# main.net
KiCad netlist of a schematic drawn in EAGLE
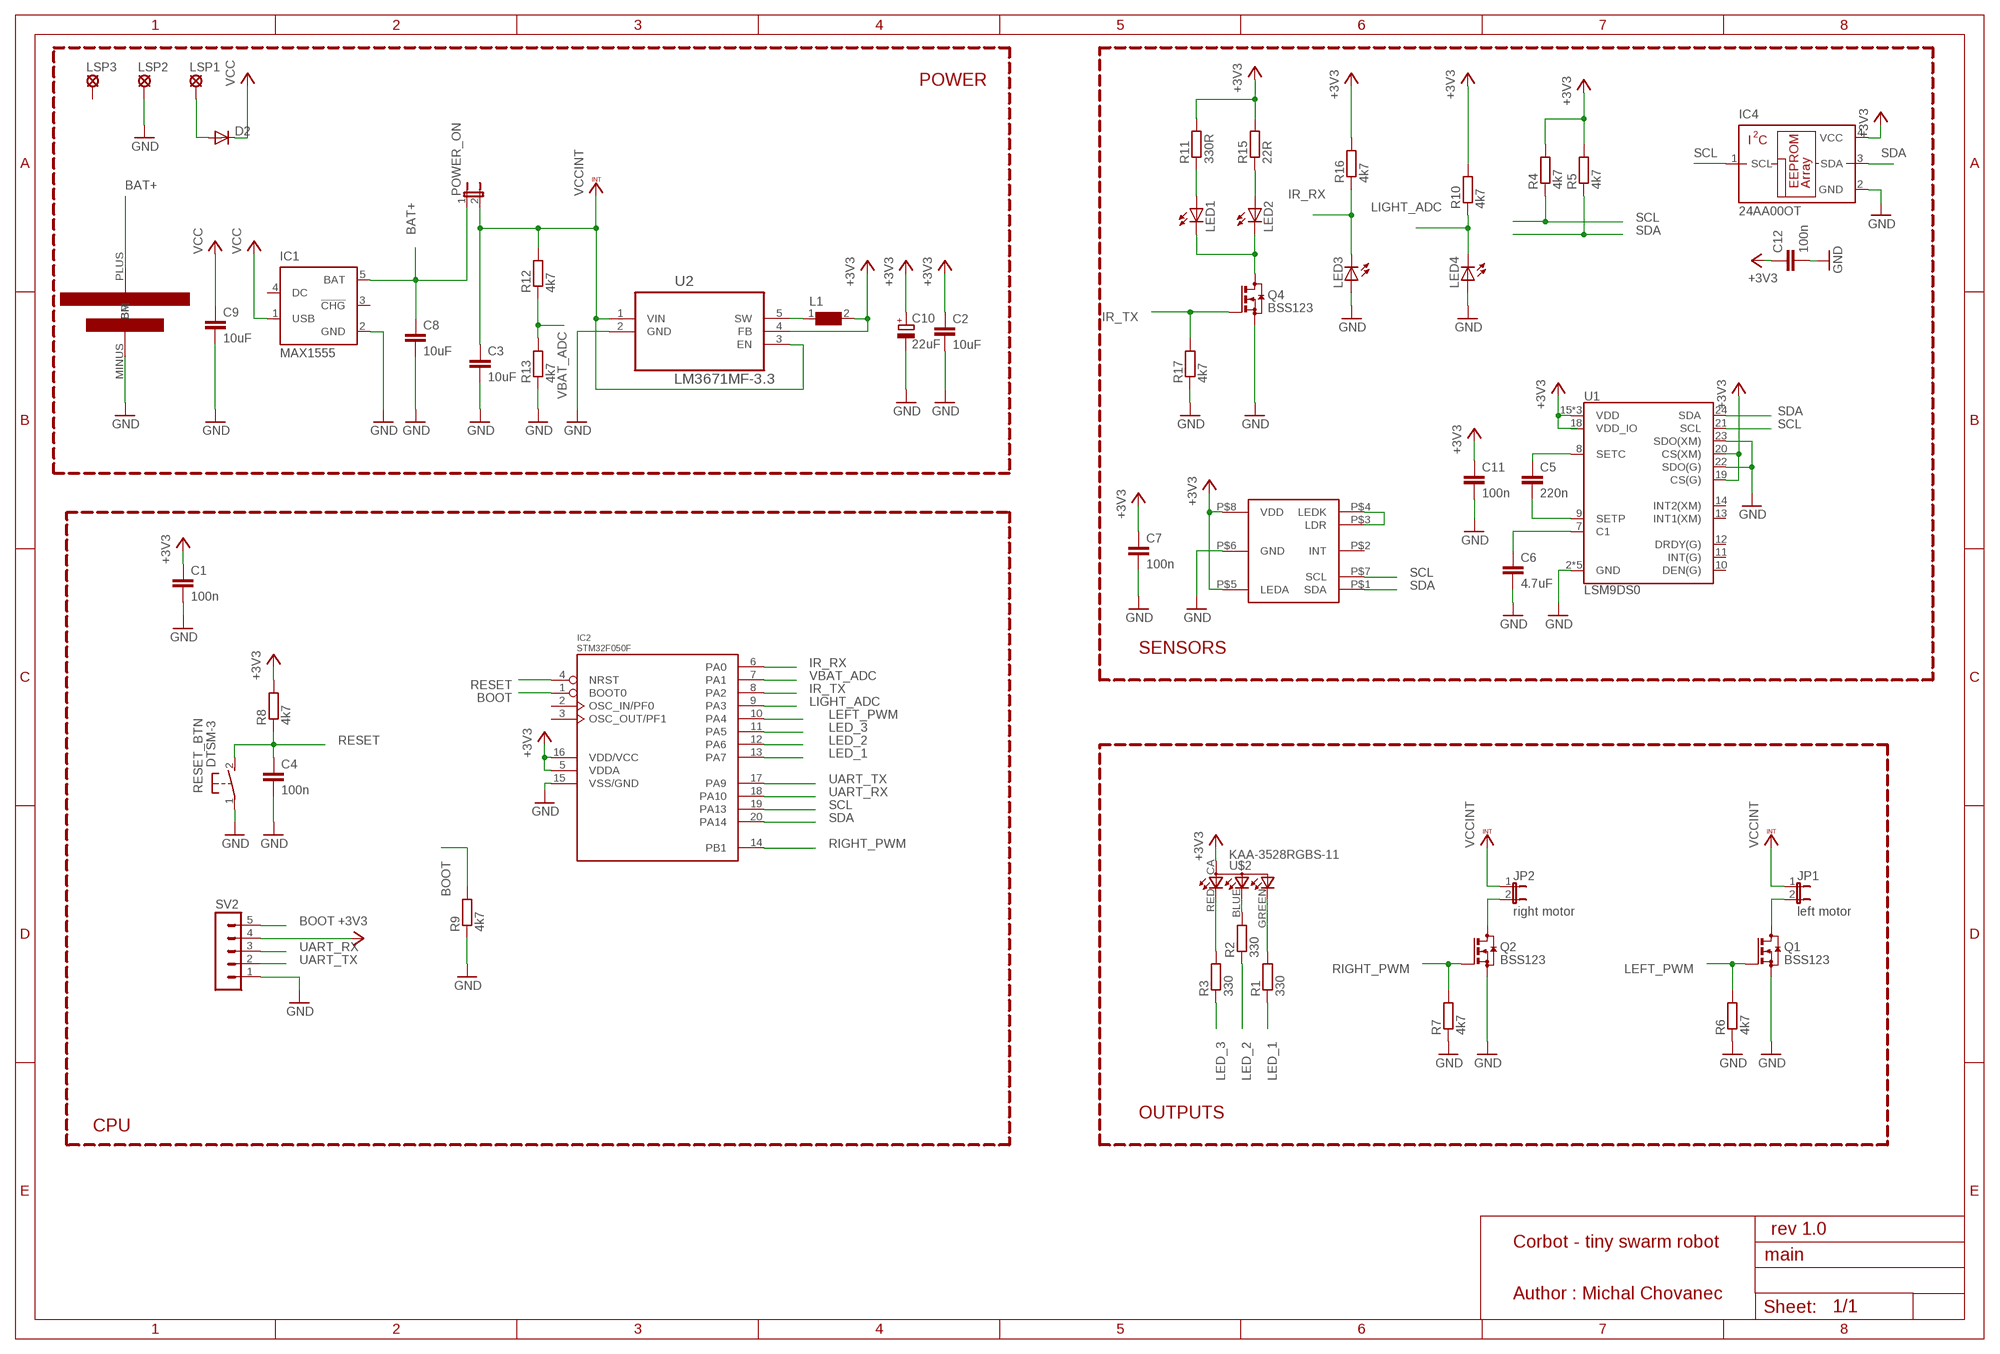
[diagram p0: schematic, sheet 1]

(export (version "E")
  (design (tool "Eeschema 10.0.6"))
  (components
    (comp (ref "C1")
      (value "100n")
      (footprint "eagle-import:C0805")
      (libsource (lib "eagle-import") (part "C-EUC0805"))
    )
    (comp (ref "C2")
      (value "10uF")
      (footprint "eagle-import:C0805")
      (libsource (lib "eagle-import") (part "C-EUC0805"))
    )
    (comp (ref "C3")
      (value "10uF")
      (footprint "eagle-import:C0805")
      (libsource (lib "eagle-import") (part "C-EUC0805"))
    )
    (comp (ref "C4")
      (value "100n")
      (footprint "eagle-import:C0805")
      (libsource (lib "eagle-import") (part "C-EUC0805"))
    )
    (comp (ref "C5")
      (value "220n")
      (footprint "eagle-import:C0805")
      (libsource (lib "eagle-import") (part "C-EUC0805"))
    )
    (comp (ref "C6")
      (value "4.7uF")
      (footprint "eagle-import:C0805")
      (libsource (lib "eagle-import") (part "C-EUC0805"))
    )
    (comp (ref "C7")
      (value "100n")
      (footprint "eagle-import:C0805")
      (libsource (lib "eagle-import") (part "C-EUC0805"))
    )
    (comp (ref "C8")
      (value "10uF")
      (footprint "eagle-import:C0805")
      (libsource (lib "eagle-import") (part "C-EUC0805"))
    )
    (comp (ref "C9")
      (value "10uF")
      (footprint "eagle-import:C0805")
      (libsource (lib "eagle-import") (part "C-EUC0805"))
    )
    (comp (ref "C10")
      (value "22uF")
      (footprint "eagle-import:153CLV-0505")
      (libsource (lib "eagle-import") (part "CPOL-EU153CLV-0505"))
    )
    (comp (ref "C11")
      (value "100n")
      (footprint "eagle-import:C0805")
      (libsource (lib "eagle-import") (part "C-EUC0805"))
    )
    (comp (ref "C12")
      (value "100n")
      (footprint "eagle-import:C0805")
      (libsource (lib "eagle-import") (part "C-EUC0805"))
    )
    (comp (ref "D2")
      (value "DIODE-DO-214AC")
      (footprint "eagle-import:DO-214AC")
      (libsource (lib "eagle-import") (part "DIODE-DO-214AC"))
    )
    (comp (ref "IC1")
      (value "MAX1555")
      (footprint "eagle-import:SOT23-5L")
      (fields (field (name "MF") "MAXIM") (field (name "MPN") "MAX1555EZK+T"))
      (libsource (lib "eagle-import") (part "MAX1555"))
    )
    (comp (ref "IC2")
      (value "STM32F050F")
      (footprint "eagle-import:TSSOP20")
      (libsource (lib "eagle-import") (part "STM32F050F"))
    )
    (comp (ref "IC4")
      (value "24AA00OT")
      (footprint "eagle-import:SOT23-5L")
      (fields (field (name "MF") "MICROCHIP") (field (name "MPN") "24AA00T-I/OTG"))
      (libsource (lib "eagle-import") (part "2400OTAA"))
    )
    (comp (ref "JP1")
      (value "left motor")
      (footprint "eagle-import:JP1")
      (libsource (lib "eagle-import") (part "JP1E"))
    )
    (comp (ref "JP2")
      (value "right motor")
      (footprint "eagle-import:JP1")
      (libsource (lib "eagle-import") (part "JP1E"))
    )
    (comp (ref "L1")
      (value "WE-LQ-744032002_M")
      (footprint "eagle-import:WE-LQ_M")
      (fields (field (name "MPN") "744032002 "))
      (libsource (lib "eagle-import") (part "WE-LQ_M-744032002"))
    )
    (comp (ref "LED1")
      (value "LEDCHIPLED_1206")
      (footprint "eagle-import:CHIPLED_1206")
      (libsource (lib "eagle-import") (part "LEDCHIPLED_1206"))
    )
    (comp (ref "LED2")
      (value "LEDCHIPLED_1206")
      (footprint "eagle-import:CHIPLED_1206")
      (libsource (lib "eagle-import") (part "LEDCHIPLED_1206"))
    )
    (comp (ref "LED3")
      (value "LEDCHIPLED_1206")
      (footprint "eagle-import:CHIPLED_1206")
      (libsource (lib "eagle-import") (part "LEDCHIPLED_1206"))
    )
    (comp (ref "LED4")
      (value "LEDCHIPLED_1206")
      (footprint "eagle-import:CHIPLED_1206")
      (libsource (lib "eagle-import") (part "LEDCHIPLED_1206"))
    )
    (comp (ref "LSP1")
      (value "LSP13")
      (footprint "eagle-import:LSP13")
      (libsource (lib "eagle-import") (part "LSP13"))
    )
    (comp (ref "LSP2")
      (value "LSP13")
      (footprint "eagle-import:LSP13")
      (libsource (lib "eagle-import") (part "LSP13"))
    )
    (comp (ref "LSP3")
      (value "LSP13")
      (footprint "eagle-import:LSP13")
      (libsource (lib "eagle-import") (part "LSP13"))
    )
    (comp (ref "POWER_ON")
      (value "JP1E")
      (footprint "eagle-import:JP1")
      (libsource (lib "eagle-import") (part "JP1E"))
    )
    (comp (ref "Q1")
      (value "BSS123")
      (footprint "eagle-import:SOT23")
      (libsource (lib "eagle-import") (part "BSS123"))
    )
    (comp (ref "Q2")
      (value "BSS123")
      (footprint "eagle-import:SOT23")
      (libsource (lib "eagle-import") (part "BSS123"))
    )
    (comp (ref "Q4")
      (value "BSS123")
      (footprint "eagle-import:SOT23")
      (libsource (lib "eagle-import") (part "BSS123"))
    )
    (comp (ref "R1")
      (value "330")
      (footprint "eagle-import:M0805")
      (libsource (lib "eagle-import") (part "R-EU_M0805"))
    )
    (comp (ref "R2")
      (value "330")
      (footprint "eagle-import:M0805")
      (libsource (lib "eagle-import") (part "R-EU_M0805"))
    )
    (comp (ref "R3")
      (value "330")
      (footprint "eagle-import:M0805")
      (libsource (lib "eagle-import") (part "R-EU_M0805"))
    )
    (comp (ref "R4")
      (value "4k7")
      (footprint "eagle-import:M0805")
      (libsource (lib "eagle-import") (part "R-EU_M0805"))
    )
    (comp (ref "R5")
      (value "4k7")
      (footprint "eagle-import:M0805")
      (libsource (lib "eagle-import") (part "R-EU_M0805"))
    )
    (comp (ref "R6")
      (value "4k7")
      (footprint "eagle-import:M0805")
      (libsource (lib "eagle-import") (part "R-EU_M0805"))
    )
    (comp (ref "R7")
      (value "4k7")
      (footprint "eagle-import:M0805")
      (libsource (lib "eagle-import") (part "R-EU_M0805"))
    )
    (comp (ref "R8")
      (value "4k7")
      (footprint "eagle-import:M0805")
      (libsource (lib "eagle-import") (part "R-EU_M0805"))
    )
    (comp (ref "R9")
      (value "4k7")
      (footprint "eagle-import:M0805")
      (libsource (lib "eagle-import") (part "R-EU_M0805"))
    )
    (comp (ref "R10")
      (value "4k7")
      (footprint "eagle-import:M0805")
      (libsource (lib "eagle-import") (part "R-EU_M0805"))
    )
    (comp (ref "R11")
      (value "330R")
      (footprint "eagle-import:M0805")
      (libsource (lib "eagle-import") (part "R-EU_M0805"))
    )
    (comp (ref "R12")
      (value "4k7")
      (footprint "eagle-import:M0805")
      (libsource (lib "eagle-import") (part "R-EU_M0805"))
    )
    (comp (ref "R13")
      (value "4k7")
      (footprint "eagle-import:M0805")
      (libsource (lib "eagle-import") (part "R-EU_M0805"))
    )
    (comp (ref "R15")
      (value "22R")
      (footprint "eagle-import:M0805")
      (libsource (lib "eagle-import") (part "R-EU_M0805"))
    )
    (comp (ref "R16")
      (value "4k7")
      (footprint "eagle-import:M0805")
      (libsource (lib "eagle-import") (part "R-EU_M0805"))
    )
    (comp (ref "R17")
      (value "4k7")
      (footprint "eagle-import:M0805")
      (libsource (lib "eagle-import") (part "R-EU_M0805"))
    )
    (comp (ref "RESET_BTN")
      (value "DTSM-3")
      (footprint "eagle-import:DTSM-3")
      (libsource (lib "eagle-import") (part "DTSM-3"))
    )
    (comp (ref "SV2")
      (value "MA05-1")
      (footprint "eagle-import:MA05-1")
      (libsource (lib "eagle-import") (part "MA05-1"))
    )
    (comp (ref "U$1")
      (value "SMTU_2450N")
      (footprint "eagle-import:SMTU_2450N")
      (libsource (lib "eagle-import") (part "SMTU_2450N"))
    )
    (comp (ref "U$2")
      (value "KAA-3528RGBS-11")
      (footprint "eagle-import:LED-RGB")
      (libsource (lib "eagle-import") (part "KAA-3528RGBS-11"))
    )
    (comp (ref "U$3")
      (value "APDS9950")
      (footprint "eagle-import:APDS9950")
      (libsource (lib "eagle-import") (part "APDS9950"))
    )
    (comp (ref "U1")
      (value "LSM9DS0")
      (footprint "eagle-import:LGA-24")
      (libsource (lib "eagle-import") (part "LSM9DS0"))
    )
    (comp (ref "U2")
      (value "LM3671MF-3.3")
      (footprint "eagle-import:SOT95P284X122-5N")
      (libsource (lib "eagle-import") (part "LM3671MF-3.3"))
    )
  )
  (nets
    (net (code "1") (name "+3V3") (class "Default")
      (node (ref "C1") (pin "1") (pinfunction "1_1") (pintype "passive"))
      (node (ref "C10") (pin "+") (pinfunction "+_+") (pintype "passive"))
      (node (ref "C11") (pin "1") (pinfunction "1_1") (pintype "passive"))
      (node (ref "C12") (pin "1") (pinfunction "1_1") (pintype "passive"))
      (node (ref "C2") (pin "1") (pinfunction "1_1") (pintype "passive"))
      (node (ref "C7") (pin "1") (pinfunction "1_1") (pintype "passive"))
      (node (ref "IC2") (pin "16") (pinfunction "VDD/VCC_16") (pintype "power_in"))
      (node (ref "IC2") (pin "5") (pinfunction "VDDA_5") (pintype "power_in"))
      (node (ref "IC4") (pin "4") (pinfunction "VCC_4") (pintype "power_in"))
      (node (ref "L1") (pin "2") (pinfunction "2_2") (pintype "passive"))
      (node (ref "R10") (pin "2") (pinfunction "2_2") (pintype "passive"))
      (node (ref "R11") (pin "2") (pinfunction "2_2") (pintype "passive"))
      (node (ref "R15") (pin "2") (pinfunction "2_2") (pintype "passive"))
      (node (ref "R16") (pin "2") (pinfunction "2_2") (pintype "passive"))
      (node (ref "R4") (pin "2") (pinfunction "2_2") (pintype "passive"))
      (node (ref "R5") (pin "2") (pinfunction "2_2") (pintype "passive"))
      (node (ref "R8") (pin "2") (pinfunction "2_2") (pintype "passive"))
      (node (ref "SV2") (pin "4") (pinfunction "4_4") (pintype "passive"))
      (node (ref "U$2") (pin "CA") (pinfunction "A_CA") (pintype "passive"))
      (node (ref "U$3") (pin "P$5") (pinfunction "LEDA_P$5") (pintype "bidirectional"))
      (node (ref "U$3") (pin "P$8") (pinfunction "VDD_P$8") (pintype "bidirectional"))
      (node (ref "U1") (pin "15") (pinfunction "VDD_15") (pintype "bidirectional"))
      (node (ref "U1") (pin "16") (pinfunction "VDD_16") (pintype "bidirectional"))
      (node (ref "U1") (pin "17") (pinfunction "VDD_17") (pintype "bidirectional"))
      (node (ref "U1") (pin "19") (pinfunction "CS(G)_19") (pintype "bidirectional"))
      (node (ref "U1") (pin "20") (pinfunction "CS(XM)_20") (pintype "bidirectional"))
      (node (ref "U2") (pin "4") (pinfunction "FB_4") (pintype "passive"))
    )
    (net (code "2") (name "/BAT+") (class "Default")
      (node (ref "C8") (pin "1") (pinfunction "1_1") (pintype "passive"))
      (node (ref "IC1") (pin "5") (pinfunction "BAT_5") (pintype "passive"))
      (node (ref "POWER_ON") (pin "1") (pinfunction "1_1") (pintype "passive"))
      (node (ref "U$1") (pin "PLUS") (pinfunction "BP_PLUS") (pintype "bidirectional"))
    )
    (net (code "3") (name "/BOOT") (class "Default")
      (node (ref "IC2") (pin "1") (pinfunction "BOOT0_1") (pintype "bidirectional"))
      (node (ref "R9") (pin "2") (pinfunction "2_2") (pintype "passive"))
      (node (ref "SV2") (pin "5") (pinfunction "5_5") (pintype "passive"))
    )
    (net (code "4") (name "/IR_RX") (class "Default")
      (node (ref "IC2") (pin "6") (pinfunction "PA0_6") (pintype "bidirectional"))
      (node (ref "LED3") (pin "C") (pinfunction "C_C") (pintype "passive"))
      (node (ref "R16") (pin "1") (pinfunction "1_1") (pintype "passive"))
    )
    (net (code "5") (name "/IR_TX") (class "Default")
      (node (ref "IC2") (pin "8") (pinfunction "PA2_8") (pintype "bidirectional"))
      (node (ref "Q4") (pin "1") (pinfunction "G_1") (pintype "passive"))
      (node (ref "R17") (pin "2") (pinfunction "2_2") (pintype "passive"))
    )
    (net (code "6") (name "/LED_1") (class "Default")
      (node (ref "IC2") (pin "13") (pinfunction "PA7_13") (pintype "bidirectional"))
      (node (ref "R1") (pin "1") (pinfunction "1_1") (pintype "passive"))
    )
    (net (code "7") (name "/LED_2") (class "Default")
      (node (ref "IC2") (pin "12") (pinfunction "PA6_12") (pintype "bidirectional"))
      (node (ref "R2") (pin "1") (pinfunction "1_1") (pintype "passive"))
    )
    (net (code "8") (name "/LED_3") (class "Default")
      (node (ref "IC2") (pin "11") (pinfunction "PA5_11") (pintype "bidirectional"))
      (node (ref "R3") (pin "1") (pinfunction "1_1") (pintype "passive"))
    )
    (net (code "9") (name "/LEFT_PWM") (class "Default")
      (node (ref "IC2") (pin "10") (pinfunction "PA4_10") (pintype "bidirectional"))
      (node (ref "Q1") (pin "1") (pinfunction "G_1") (pintype "passive"))
      (node (ref "R6") (pin "2") (pinfunction "2_2") (pintype "passive"))
    )
    (net (code "10") (name "/LIGHT_ADC") (class "Default")
      (node (ref "IC2") (pin "9") (pinfunction "PA3_9") (pintype "bidirectional"))
      (node (ref "LED4") (pin "C") (pinfunction "C_C") (pintype "passive"))
      (node (ref "R10") (pin "1") (pinfunction "1_1") (pintype "passive"))
    )
    (net (code "11") (name "/RESET") (class "Default")
      (node (ref "C4") (pin "1") (pinfunction "1_1") (pintype "passive"))
      (node (ref "IC2") (pin "4") (pinfunction "NRST_4") (pintype "bidirectional"))
      (node (ref "R8") (pin "1") (pinfunction "1_1") (pintype "passive"))
      (node (ref "RESET_BTN") (pin "2") (pinfunction "2_2") (pintype "passive"))
    )
    (net (code "12") (name "/RIGHT_PWM") (class "Default")
      (node (ref "IC2") (pin "14") (pinfunction "PB1_14") (pintype "bidirectional"))
      (node (ref "Q2") (pin "1") (pinfunction "G_1") (pintype "passive"))
      (node (ref "R7") (pin "2") (pinfunction "2_2") (pintype "passive"))
    )
    (net (code "13") (name "/SCL") (class "Default")
      (node (ref "IC2") (pin "19") (pinfunction "PA13_19") (pintype "bidirectional"))
      (node (ref "IC4") (pin "1") (pinfunction "SCL_1") (pintype "input"))
      (node (ref "R4") (pin "1") (pinfunction "1_1") (pintype "passive"))
      (node (ref "U$3") (pin "P$7") (pinfunction "SCL_P$7") (pintype "bidirectional"))
      (node (ref "U1") (pin "21") (pinfunction "SCL_21") (pintype "bidirectional"))
    )
    (net (code "14") (name "/SDA") (class "Default")
      (node (ref "IC2") (pin "20") (pinfunction "PA14_20") (pintype "bidirectional"))
      (node (ref "IC4") (pin "3") (pinfunction "SDA_3") (pintype "bidirectional"))
      (node (ref "R5") (pin "1") (pinfunction "1_1") (pintype "passive"))
      (node (ref "U$3") (pin "P$1") (pinfunction "SDA_P$1") (pintype "bidirectional"))
      (node (ref "U1") (pin "24") (pinfunction "SDA_24") (pintype "bidirectional"))
    )
    (net (code "15") (name "/UART_RX") (class "Default")
      (node (ref "IC2") (pin "18") (pinfunction "PA10_18") (pintype "bidirectional"))
      (node (ref "SV2") (pin "3") (pinfunction "3_3") (pintype "passive"))
    )
    (net (code "16") (name "/UART_TX") (class "Default")
      (node (ref "IC2") (pin "17") (pinfunction "PA9_17") (pintype "bidirectional"))
      (node (ref "SV2") (pin "2") (pinfunction "2_2") (pintype "passive"))
    )
    (net (code "17") (name "/VBAT_ADC") (class "Default")
      (node (ref "IC2") (pin "7") (pinfunction "PA1_7") (pintype "bidirectional"))
      (node (ref "R12") (pin "1") (pinfunction "1_1") (pintype "passive"))
      (node (ref "R13") (pin "2") (pinfunction "2_2") (pintype "passive"))
    )
    (net (code "18") (name "GND") (class "Default")
      (node (ref "C1") (pin "2") (pinfunction "2_2") (pintype "passive"))
      (node (ref "C10") (pin "-") (pinfunction "-_-") (pintype "passive"))
      (node (ref "C11") (pin "2") (pinfunction "2_2") (pintype "passive"))
      (node (ref "C12") (pin "2") (pinfunction "2_2") (pintype "passive"))
      (node (ref "C2") (pin "2") (pinfunction "2_2") (pintype "passive"))
      (node (ref "C3") (pin "2") (pinfunction "2_2") (pintype "passive"))
      (node (ref "C4") (pin "2") (pinfunction "2_2") (pintype "passive"))
      (node (ref "C6") (pin "2") (pinfunction "2_2") (pintype "passive"))
      (node (ref "C7") (pin "2") (pinfunction "2_2") (pintype "passive"))
      (node (ref "C8") (pin "2") (pinfunction "2_2") (pintype "passive"))
      (node (ref "C9") (pin "2") (pinfunction "2_2") (pintype "passive"))
      (node (ref "IC1") (pin "2") (pinfunction "GND_2") (pintype "power_in"))
      (node (ref "IC2") (pin "15") (pinfunction "VSS/GND_15") (pintype "power_in"))
      (node (ref "IC4") (pin "2") (pinfunction "GND_2") (pintype "power_in"))
      (node (ref "LED3") (pin "A") (pinfunction "A_A") (pintype "passive"))
      (node (ref "LED4") (pin "A") (pinfunction "A_A") (pintype "passive"))
      (node (ref "LSP2") (pin "MP") (pinfunction "MP_MP") (pintype "passive"))
      (node (ref "Q1") (pin "2") (pinfunction "S_2") (pintype "passive"))
      (node (ref "Q2") (pin "2") (pinfunction "S_2") (pintype "passive"))
      (node (ref "Q4") (pin "2") (pinfunction "S_2") (pintype "passive"))
      (node (ref "R13") (pin "1") (pinfunction "1_1") (pintype "passive"))
      (node (ref "R17") (pin "1") (pinfunction "1_1") (pintype "passive"))
      (node (ref "R6") (pin "1") (pinfunction "1_1") (pintype "passive"))
      (node (ref "R7") (pin "1") (pinfunction "1_1") (pintype "passive"))
      (node (ref "R9") (pin "1") (pinfunction "1_1") (pintype "passive"))
      (node (ref "RESET_BTN") (pin "1") (pinfunction "1_1") (pintype "passive"))
      (node (ref "SV2") (pin "1") (pinfunction "1_1") (pintype "passive"))
      (node (ref "U$1") (pin "MINUS") (pinfunction "BM_MINUS") (pintype "bidirectional"))
      (node (ref "U$3") (pin "P$6") (pinfunction "GND_P$6") (pintype "bidirectional"))
      (node (ref "U1") (pin "2") (pinfunction "GND_2") (pintype "bidirectional"))
      (node (ref "U1") (pin "22") (pinfunction "SDO(G)_22") (pintype "bidirectional"))
      (node (ref "U1") (pin "23") (pinfunction "SDO(XM)_23") (pintype "bidirectional"))
      (node (ref "U1") (pin "3") (pinfunction "GND_3") (pintype "bidirectional"))
      (node (ref "U1") (pin "4") (pinfunction "GND_4") (pintype "bidirectional"))
      (node (ref "U1") (pin "5") (pinfunction "GND_5") (pintype "bidirectional"))
      (node (ref "U1") (pin "6") (pinfunction "GND_6") (pintype "bidirectional"))
      (node (ref "U2") (pin "2") (pinfunction "GND_2") (pintype "passive"))
    )
    (net (code "19") (name "Net-(D2-PadA)") (class "Default")
      (node (ref "D2") (pin "A") (pinfunction "A_A") (pintype "passive"))
      (node (ref "LSP1") (pin "MP") (pinfunction "MP_MP") (pintype "passive"))
    )
    (net (code "20") (name "Net-(LED1-PadA)") (class "Default")
      (node (ref "LED1") (pin "A") (pinfunction "A_A") (pintype "passive"))
      (node (ref "R11") (pin "1") (pinfunction "1_1") (pintype "passive"))
    )
    (net (code "21") (name "Net-(LED2-PadA)") (class "Default")
      (node (ref "LED2") (pin "A") (pinfunction "A_A") (pintype "passive"))
      (node (ref "R15") (pin "1") (pinfunction "1_1") (pintype "passive"))
    )
    (net (code "22") (name "Net-(Q1-D)") (class "Default")
      (node (ref "JP1") (pin "2") (pinfunction "2_2") (pintype "passive"))
      (node (ref "Q1") (pin "3") (pinfunction "D_3") (pintype "passive"))
    )
    (net (code "23") (name "Net-(Q2-D)") (class "Default")
      (node (ref "JP2") (pin "2") (pinfunction "2_2") (pintype "passive"))
      (node (ref "Q2") (pin "3") (pinfunction "D_3") (pintype "passive"))
    )
    (net (code "24") (name "Net-(Q4-D)") (class "Default")
      (node (ref "LED1") (pin "C") (pinfunction "C_C") (pintype "passive"))
      (node (ref "LED2") (pin "C") (pinfunction "C_C") (pintype "passive"))
      (node (ref "Q4") (pin "3") (pinfunction "D_3") (pintype "passive"))
    )
    (net (code "25") (name "Net-(U$2-CBLUE)") (class "Default")
      (node (ref "R2") (pin "2") (pinfunction "2_2") (pintype "passive"))
      (node (ref "U$2") (pin "BLUE") (pinfunction "CBLUE_BLUE") (pintype "passive"))
    )
    (net (code "26") (name "Net-(U$2-CGREEN)") (class "Default")
      (node (ref "R1") (pin "2") (pinfunction "2_2") (pintype "passive"))
      (node (ref "U$2") (pin "GREEN") (pinfunction "CGREEN_GREEN") (pintype "passive"))
    )
    (net (code "27") (name "Net-(U$2-CRED)") (class "Default")
      (node (ref "R3") (pin "2") (pinfunction "2_2") (pintype "passive"))
      (node (ref "U$2") (pin "RED") (pinfunction "CRED_RED") (pintype "passive"))
    )
    (net (code "28") (name "Net-(U$3-LDR)") (class "Default")
      (node (ref "U$3") (pin "P$3") (pinfunction "LDR_P$3") (pintype "bidirectional"))
      (node (ref "U$3") (pin "P$4") (pinfunction "LEDK_P$4") (pintype "bidirectional"))
    )
    (net (code "29") (name "Net-(U1-C1)") (class "Default")
      (node (ref "C6") (pin "1") (pinfunction "1_1") (pintype "passive"))
      (node (ref "U1") (pin "7") (pinfunction "C1_7") (pintype "bidirectional"))
    )
    (net (code "30") (name "Net-(U1-SETC)") (class "Default")
      (node (ref "C5") (pin "1") (pinfunction "1_1") (pintype "passive"))
      (node (ref "U1") (pin "8") (pinfunction "SETC_8") (pintype "bidirectional"))
    )
    (net (code "31") (name "Net-(U1-SETP)") (class "Default")
      (node (ref "C5") (pin "2") (pinfunction "2_2") (pintype "passive"))
      (node (ref "U1") (pin "9") (pinfunction "SETP_9") (pintype "bidirectional"))
    )
    (net (code "32") (name "Net-(U2-SW)") (class "Default")
      (node (ref "L1") (pin "1") (pinfunction "1_1") (pintype "passive"))
      (node (ref "U2") (pin "5") (pinfunction "SW_5") (pintype "output"))
    )
    (net (code "33") (name "VCC") (class "Default")
      (node (ref "C9") (pin "1") (pinfunction "1_1") (pintype "passive"))
      (node (ref "D2") (pin "C") (pinfunction "C_C") (pintype "passive"))
      (node (ref "IC1") (pin "1") (pinfunction "USB_1") (pintype "input"))
    )
    (net (code "34") (name "VCCINT") (class "Default")
      (node (ref "C3") (pin "1") (pinfunction "1_1") (pintype "passive"))
      (node (ref "JP1") (pin "1") (pinfunction "1_1") (pintype "passive"))
      (node (ref "JP2") (pin "1") (pinfunction "1_1") (pintype "passive"))
      (node (ref "POWER_ON") (pin "2") (pinfunction "2_2") (pintype "passive"))
      (node (ref "R12") (pin "2") (pinfunction "2_2") (pintype "passive"))
      (node (ref "U2") (pin "1") (pinfunction "VIN_1") (pintype "input"))
      (node (ref "U2") (pin "3") (pinfunction "EN_3") (pintype "passive"))
    )
    (net (code "35") (name "unconnected-(IC1-DC-Pad4)") (class "Default")
      (node (ref "IC1") (pin "4") (pinfunction "DC_4") (pintype "input"))
    )
    (net (code "36") (name "unconnected-(IC1-~{CHG}-Pad3)") (class "Default")
      (node (ref "IC1") (pin "3") (pinfunction "~{CHG}_3") (pintype "output"))
    )
    (net (code "37") (name "unconnected-(IC2-OSC_IN{slash}PF0-Pad2)") (class "Default")
      (node (ref "IC2") (pin "2") (pinfunction "OSC_IN/PF0_2") (pintype "bidirectional"))
    )
    (net (code "38") (name "unconnected-(IC2-OSC_OUT{slash}PF1-Pad3)") (class "Default")
      (node (ref "IC2") (pin "3") (pinfunction "OSC_OUT/PF1_3") (pintype "bidirectional"))
    )
    (net (code "39") (name "unconnected-(LSP3-PadMP)") (class "Default")
      (node (ref "LSP3") (pin "MP") (pinfunction "MP_MP") (pintype "passive"))
    )
    (net (code "40") (name "unconnected-(U$3-INT-PadP$2)") (class "Default")
      (node (ref "U$3") (pin "P$2") (pinfunction "INT_P$2") (pintype "bidirectional"))
    )
    (net (code "41") (name "unconnected-(U1-DEN(G)-Pad10)") (class "Default")
      (node (ref "U1") (pin "10") (pinfunction "DEN(G)_10") (pintype "bidirectional"))
    )
    (net (code "42") (name "unconnected-(U1-DRDY(G)-Pad12)") (class "Default")
      (node (ref "U1") (pin "12") (pinfunction "DRDY(G)_12") (pintype "bidirectional"))
    )
    (net (code "43") (name "unconnected-(U1-INT(G)-Pad11)") (class "Default")
      (node (ref "U1") (pin "11") (pinfunction "INT(G)_11") (pintype "bidirectional"))
    )
    (net (code "44") (name "unconnected-(U1-INT1(XM)-Pad13)") (class "Default")
      (node (ref "U1") (pin "13") (pinfunction "INT1(XM)_13") (pintype "bidirectional"))
    )
    (net (code "45") (name "unconnected-(U1-INT2(XM)-Pad14)") (class "Default")
      (node (ref "U1") (pin "14") (pinfunction "INT2(XM)_14") (pintype "bidirectional"))
    )
    (net (code "46") (name "unconnected-(U1-VDD_IO-Pad18)") (class "Default")
      (node (ref "U1") (pin "18") (pinfunction "VDD_IO_18") (pintype "bidirectional"))
    )
  )
)
